# Power_Distribution_-_Power_Path_DCDC_MOS.net
KiCad netlist of a schematic drawn in Altium Designer
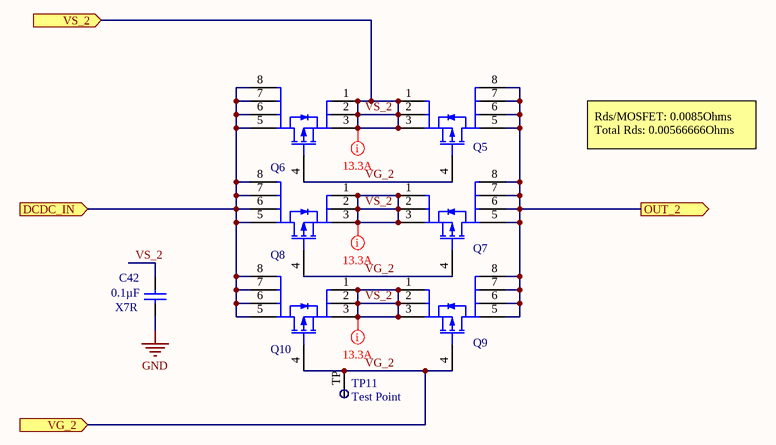
[diagram p0: Power Distribution - Power Path DCDC MOSFET.SchDoc]

(export (version "E")
  (design (tool "Eeschema 10.0.6"))
  (components
    (comp (ref "C42")
      (value "CAP CER 0.1UF 50V 10% X7R 0603")
      (footprint "CAP, 0603")
      (description "0.10µF ±10% 50V Ceramic Capacitor X7R 0603 (1608 Metric)")
      (fields
        (field (name "TOLERANCE") "±10%")
        (field (name "CAPACITANCE") "0.1µF")
        (field (name "TEMPERATURE COEFFICIENT") "X7R")
        (field (name "VOLTAGE") "50V")
      )
      (libsource (lib "Schematic Diagrams") (part "CAP CER 0.1UF 50V 10% X7R 0603"))
    )
    (comp (ref "Q5")
      (value "MOSFET P-CH PWR56 40V 4.9 MOHM")
      (footprint "PMOS PWR56 40V 4.9 MOHM")
      (description "P-Channel 16V 2.5A (Ta) 650mW (Ta) Surface Mount X2-DFN2015-3")
      (libsource (lib "Schematic Diagrams") (part "MOSFET P-CH PWR56 40V 4.9 MOHM"))
    )
    (comp (ref "Q6")
      (value "MOSFET P-CH PWR56 40V 4.9 MOHM")
      (footprint "PMOS PWR56 40V 4.9 MOHM")
      (description "P-Channel 16V 2.5A (Ta) 650mW (Ta) Surface Mount X2-DFN2015-3")
      (libsource (lib "Schematic Diagrams") (part "MOSFET P-CH PWR56 40V 4.9 MOHM"))
    )
    (comp (ref "Q7")
      (value "MOSFET P-CH PWR56 40V 4.9 MOHM")
      (footprint "PMOS PWR56 40V 4.9 MOHM")
      (description "P-Channel 16V 2.5A (Ta) 650mW (Ta) Surface Mount X2-DFN2015-3")
      (libsource (lib "Schematic Diagrams") (part "MOSFET P-CH PWR56 40V 4.9 MOHM"))
    )
    (comp (ref "Q8")
      (value "MOSFET P-CH PWR56 40V 4.9 MOHM")
      (footprint "PMOS PWR56 40V 4.9 MOHM")
      (description "P-Channel 16V 2.5A (Ta) 650mW (Ta) Surface Mount X2-DFN2015-3")
      (libsource (lib "Schematic Diagrams") (part "MOSFET P-CH PWR56 40V 4.9 MOHM"))
    )
    (comp (ref "Q9")
      (value "MOSFET P-CH PWR56 40V 4.9 MOHM")
      (footprint "PMOS PWR56 40V 4.9 MOHM")
      (description "P-Channel 16V 2.5A (Ta) 650mW (Ta) Surface Mount X2-DFN2015-3")
      (libsource (lib "Schematic Diagrams") (part "MOSFET P-CH PWR56 40V 4.9 MOHM"))
    )
    (comp (ref "Q10")
      (value "MOSFET P-CH PWR56 40V 4.9 MOHM")
      (footprint "PMOS PWR56 40V 4.9 MOHM")
      (description "P-Channel 16V 2.5A (Ta) 650mW (Ta) Surface Mount X2-DFN2015-3")
      (libsource (lib "Schematic Diagrams") (part "MOSFET P-CH PWR56 40V 4.9 MOHM"))
    )
    (comp (ref "TP11")
      (value "Test Point")
      (footprint "Test Point")
      (libsource (lib "Schematic Diagrams") (part "Test Point"))
    )
  )
  (nets
    (net (code "1") (name "/DCDC_IN") (class "Default")
      (node (ref "Q10") (pin "5") (pinfunction "D_5") (pintype "passive"))
      (node (ref "Q10") (pin "6") (pinfunction "D_6") (pintype "passive"))
      (node (ref "Q10") (pin "7") (pinfunction "D_7") (pintype "passive"))
      (node (ref "Q10") (pin "8") (pinfunction "D_8") (pintype "passive"))
      (node (ref "Q6") (pin "5") (pinfunction "D_5") (pintype "passive"))
      (node (ref "Q6") (pin "6") (pinfunction "D_6") (pintype "passive"))
      (node (ref "Q6") (pin "7") (pinfunction "D_7") (pintype "passive"))
      (node (ref "Q6") (pin "8") (pinfunction "D_8") (pintype "passive"))
      (node (ref "Q8") (pin "5") (pinfunction "D_5") (pintype "passive"))
      (node (ref "Q8") (pin "6") (pinfunction "D_6") (pintype "passive"))
      (node (ref "Q8") (pin "7") (pinfunction "D_7") (pintype "passive"))
      (node (ref "Q8") (pin "8") (pinfunction "D_8") (pintype "passive"))
    )
    (net (code "2") (name "/OUT_2") (class "Default")
      (node (ref "Q5") (pin "5") (pinfunction "D_5") (pintype "passive"))
      (node (ref "Q5") (pin "6") (pinfunction "D_6") (pintype "passive"))
      (node (ref "Q5") (pin "7") (pinfunction "D_7") (pintype "passive"))
      (node (ref "Q5") (pin "8") (pinfunction "D_8") (pintype "passive"))
      (node (ref "Q7") (pin "5") (pinfunction "D_5") (pintype "passive"))
      (node (ref "Q7") (pin "6") (pinfunction "D_6") (pintype "passive"))
      (node (ref "Q7") (pin "7") (pinfunction "D_7") (pintype "passive"))
      (node (ref "Q7") (pin "8") (pinfunction "D_8") (pintype "passive"))
      (node (ref "Q9") (pin "5") (pinfunction "D_5") (pintype "passive"))
      (node (ref "Q9") (pin "6") (pinfunction "D_6") (pintype "passive"))
      (node (ref "Q9") (pin "7") (pinfunction "D_7") (pintype "passive"))
      (node (ref "Q9") (pin "8") (pinfunction "D_8") (pintype "passive"))
    )
    (net (code "3") (name "/VG_2") (class "Default")
      (node (ref "Q10") (pin "4") (pinfunction "G_4") (pintype "passive"))
      (node (ref "Q5") (pin "4") (pinfunction "G_4") (pintype "passive"))
      (node (ref "Q6") (pin "4") (pinfunction "G_4") (pintype "passive"))
      (node (ref "Q7") (pin "4") (pinfunction "G_4") (pintype "passive"))
      (node (ref "Q8") (pin "4") (pinfunction "G_4") (pintype "passive"))
      (node (ref "Q9") (pin "4") (pinfunction "G_4") (pintype "passive"))
      (node (ref "TP11") (pin "TP") (pinfunction "1_TP") (pintype "passive"))
    )
    (net (code "4") (name "/VS_2") (class "Default")
      (node (ref "C42") (pin "1") (pinfunction "1_1") (pintype "passive"))
      (node (ref "Q10") (pin "1") (pinfunction "S_1") (pintype "passive"))
      (node (ref "Q10") (pin "2") (pinfunction "S_2") (pintype "passive"))
      (node (ref "Q10") (pin "3") (pinfunction "S_3") (pintype "passive"))
      (node (ref "Q5") (pin "1") (pinfunction "S_1") (pintype "passive"))
      (node (ref "Q5") (pin "2") (pinfunction "S_2") (pintype "passive"))
      (node (ref "Q5") (pin "3") (pinfunction "S_3") (pintype "passive"))
      (node (ref "Q6") (pin "1") (pinfunction "S_1") (pintype "passive"))
      (node (ref "Q6") (pin "2") (pinfunction "S_2") (pintype "passive"))
      (node (ref "Q6") (pin "3") (pinfunction "S_3") (pintype "passive"))
      (node (ref "Q7") (pin "1") (pinfunction "S_1") (pintype "passive"))
      (node (ref "Q7") (pin "2") (pinfunction "S_2") (pintype "passive"))
      (node (ref "Q7") (pin "3") (pinfunction "S_3") (pintype "passive"))
      (node (ref "Q8") (pin "1") (pinfunction "S_1") (pintype "passive"))
      (node (ref "Q8") (pin "2") (pinfunction "S_2") (pintype "passive"))
      (node (ref "Q8") (pin "3") (pinfunction "S_3") (pintype "passive"))
      (node (ref "Q9") (pin "1") (pinfunction "S_1") (pintype "passive"))
      (node (ref "Q9") (pin "2") (pinfunction "S_2") (pintype "passive"))
      (node (ref "Q9") (pin "3") (pinfunction "S_3") (pintype "passive"))
    )
    (net (code "5") (name "GND") (class "Default")
      (node (ref "C42") (pin "2") (pinfunction "2_2") (pintype "passive"))
    )
  )
)
